# UWB_Control.net
KiCad netlist of a schematic drawn in Altium Designer
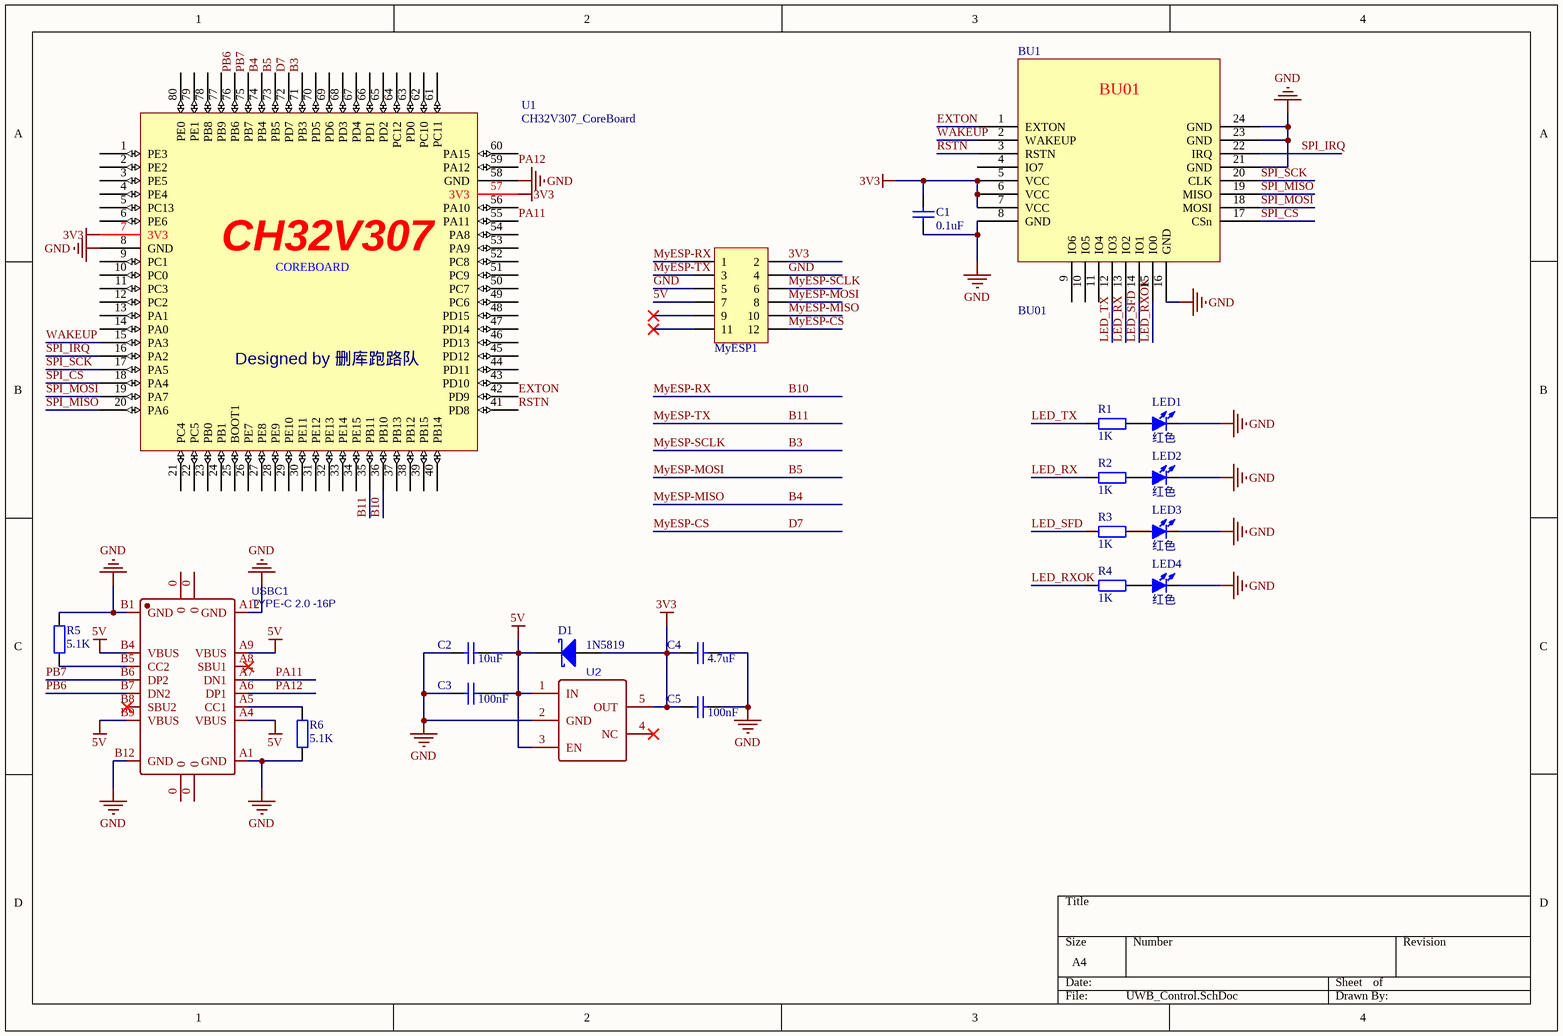
[diagram p0: UWB_Control.SchDoc]

(export (version "E")
  (design (tool "Eeschema 10.0.6"))
  (components
    (comp (ref "BU1") (value "BU01") (footprint "BU01 - duplicate") (libsource (lib "MySch") (part "BU01")))
    (comp (ref "C1")
      (value "0.1uF")
      (footprint "C0805_L")
      (description "贴片电容/MLCC电容")
      (libsource (lib "0.1 - 电阻-电容-电感-晶振-晶体-磁珠-电位器-法拉电容-馈通电容") (part "C"))
    )
    (comp (ref "C2")
      (value "10uF")
      (footprint "C0805_L")
      (description "贴片电容/MLCC电容")
      (libsource (lib "0.1 - 电阻-电容-电感-晶振-晶体-磁珠-电位器-法拉电容-馈通电容") (part "C"))
    )
    (comp (ref "C3")
      (value "100nF")
      (footprint "C0805_L")
      (description "贴片电容/MLCC电容")
      (libsource (lib "0.1 - 电阻-电容-电感-晶振-晶体-磁珠-电位器-法拉电容-馈通电容") (part "C"))
    )
    (comp (ref "C4")
      (value "4.7uF")
      (footprint "C0805_L")
      (description "贴片电容/MLCC电容")
      (libsource (lib "0.1 - 电阻-电容-电感-晶振-晶体-磁珠-电位器-法拉电容-馈通电容") (part "C"))
    )
    (comp (ref "C5")
      (value "100nF")
      (footprint "C0805_L")
      (description "贴片电容/MLCC电容")
      (libsource (lib "0.1 - 电阻-电容-电感-晶振-晶体-磁珠-电位器-法拉电容-馈通电容") (part "C"))
    )
    (comp (ref "D1")
      (value "1N5819")
      (footprint "SOD-323")
      (description "肖特基二极管")
      (libsource (lib "0.2 - 二极管-TVS-ESD-整流桥-放电管") (part "SS14"))
    )
    (comp (ref "LED1")
      (value "红色")
      (footprint "LED0805_G")
      (description "贴片LED")
      (libsource (lib "0.3 - LED发光二极管-IR二极管_接收管-光耦") (part "LED-SMD"))
    )
    (comp (ref "LED2")
      (value "红色")
      (footprint "LED0805_G")
      (description "贴片LED")
      (libsource (lib "0.3 - LED发光二极管-IR二极管_接收管-光耦") (part "LED-SMD"))
    )
    (comp (ref "LED3")
      (value "红色")
      (footprint "LED0805_G")
      (description "贴片LED")
      (libsource (lib "0.3 - LED发光二极管-IR二极管_接收管-光耦") (part "LED-SMD"))
    )
    (comp (ref "LED4")
      (value "红色")
      (footprint "LED0805_G")
      (description "贴片LED")
      (libsource (lib "0.3 - LED发光二极管-IR二极管_接收管-光耦") (part "LED-SMD"))
    )
    (comp (ref "MyESP1")
      (value "Header 6X2")
      (footprint "HDR2.54-M-LS-2x6P")
      (description "6*2P接插件")
      (fields (field (name "版权归属") "封装库来自淘宝 ID：黄晶宝石"))
      (libsource (lib "5.4 - 接插件-脚距2.54 (100mil) ") (part "Header  6X2"))
    )
    (comp (ref "R1")
      (value "1K")
      (footprint "R0805_L")
      (description "贴片电阻")
      (libsource (lib "0.1 - 电阻-电容-电感-晶振-晶体-磁珠-电位器-法拉电容-馈通电容") (part "R"))
    )
    (comp (ref "R2")
      (value "1K")
      (footprint "R0805_L")
      (description "贴片电阻")
      (libsource (lib "0.1 - 电阻-电容-电感-晶振-晶体-磁珠-电位器-法拉电容-馈通电容") (part "R"))
    )
    (comp (ref "R3")
      (value "1K")
      (footprint "R0805_L")
      (description "贴片电阻")
      (libsource (lib "0.1 - 电阻-电容-电感-晶振-晶体-磁珠-电位器-法拉电容-馈通电容") (part "R"))
    )
    (comp (ref "R4")
      (value "1K")
      (footprint "R0805_L")
      (description "贴片电阻")
      (libsource (lib "0.1 - 电阻-电容-电感-晶振-晶体-磁珠-电位器-法拉电容-馈通电容") (part "R"))
    )
    (comp (ref "R5")
      (value "5.1K")
      (footprint "R0402_L")
      (description "贴片电阻")
      (libsource (lib "0.1 - 电阻-电容-电感-晶振-晶体-磁珠-电位器-法拉电容-馈通电容") (part "R"))
    )
    (comp (ref "R6")
      (value "5.1K")
      (footprint "R0402_L")
      (description "贴片电阻")
      (libsource (lib "0.1 - 电阻-电容-电感-晶振-晶体-磁珠-电位器-法拉电容-馈通电容") (part "R"))
    )
    (comp (ref "U1")
      (value "CH32V307_CoreBoard")
      (footprint "CH32V307_PCB")
      (libsource (lib "CH32V307_SCH") (part "CH32V307_CoreBoard"))
    )
    (comp (ref "U2")
      (value "~")
      (footprint "SOT23-5")
      (libsource (lib "altium-import") (part "root_0_RT9013-33_"))
    )
    (comp (ref "USBC1")
      (value "TYPE-C 2.0 -16P")
      (footprint "USB-C-SMD_TYPE-C-USB-5")
      (description "USB2.0 Type-C 母座 16Pin")
      (libsource (lib "0.8 - 以太网-音频-USB插座") (part "USB2.0 Type-C 16Pin母座"))
    )
  )
  (nets
    (net (code "1") (name "/B3") (class "Default")
      (node (ref "MyESP1") (pin "6") (pinfunction "6_6") (pintype "passive"))
      (node (ref "U1") (pin "71") (pinfunction "PB3_71") (pintype "bidirectional"))
    )
    (net (code "2") (name "/B4") (class "Default")
      (node (ref "MyESP1") (pin "10") (pinfunction "10_10") (pintype "passive"))
      (node (ref "U1") (pin "74") (pinfunction "PB4_74") (pintype "bidirectional"))
    )
    (net (code "3") (name "/B5") (class "Default")
      (node (ref "MyESP1") (pin "8") (pinfunction "8_8") (pintype "passive"))
      (node (ref "U1") (pin "73") (pinfunction "PB5_73") (pintype "bidirectional"))
    )
    (net (code "4") (name "/B10") (class "Default")
      (node (ref "MyESP1") (pin "1") (pinfunction "1_1") (pintype "passive"))
      (node (ref "U1") (pin "36") (pinfunction "PB10_36") (pintype "bidirectional"))
    )
    (net (code "5") (name "/B11") (class "Default")
      (node (ref "MyESP1") (pin "3") (pinfunction "3_3") (pintype "passive"))
      (node (ref "U1") (pin "35") (pinfunction "PB11_35") (pintype "bidirectional"))
    )
    (net (code "6") (name "/D7") (class "Default")
      (node (ref "MyESP1") (pin "12") (pinfunction "12_12") (pintype "passive"))
      (node (ref "U1") (pin "72") (pinfunction "PD7_72") (pintype "bidirectional"))
    )
    (net (code "7") (name "/EXTON") (class "Default")
      (node (ref "BU1") (pin "1") (pinfunction "EXTON_1") (pintype "passive"))
      (node (ref "U1") (pin "42") (pinfunction "PD9_42") (pintype "bidirectional"))
    )
    (net (code "8") (name "/LED_RX") (class "Default")
      (node (ref "BU1") (pin "13") (pinfunction "IO2_13") (pintype "passive"))
      (node (ref "R2") (pin "1") (pinfunction "1_1") (pintype "passive"))
    )
    (net (code "9") (name "/LED_RXOK") (class "Default")
      (node (ref "BU1") (pin "15") (pinfunction "IO0_15") (pintype "passive"))
      (node (ref "R4") (pin "1") (pinfunction "1_1") (pintype "passive"))
    )
    (net (code "10") (name "/LED_SFD") (class "Default")
      (node (ref "BU1") (pin "14") (pinfunction "IO1_14") (pintype "passive"))
      (node (ref "R3") (pin "1") (pinfunction "1_1") (pintype "passive"))
    )
    (net (code "11") (name "/LED_TX") (class "Default")
      (node (ref "BU1") (pin "12") (pinfunction "IO3_12") (pintype "passive"))
      (node (ref "R1") (pin "1") (pinfunction "1_1") (pintype "passive"))
    )
    (net (code "12") (name "/PA11") (class "Default")
      (node (ref "U1") (pin "55") (pinfunction "PA11_55") (pintype "bidirectional"))
      (node (ref "USBC1") (pin "A7") (pinfunction "DN1_A7") (pintype "passive"))
    )
    (net (code "13") (name "/PA12") (class "Default")
      (node (ref "U1") (pin "59") (pinfunction "PA12_59") (pintype "bidirectional"))
      (node (ref "USBC1") (pin "A6") (pinfunction "DP1_A6") (pintype "passive"))
    )
    (net (code "14") (name "/PB6") (class "Default")
      (node (ref "U1") (pin "76") (pinfunction "PB6_76") (pintype "bidirectional"))
      (node (ref "USBC1") (pin "B7") (pinfunction "DN2_B7") (pintype "passive"))
    )
    (net (code "15") (name "/PB7") (class "Default")
      (node (ref "U1") (pin "75") (pinfunction "PB7_75") (pintype "bidirectional"))
      (node (ref "USBC1") (pin "B6") (pinfunction "DP2_B6") (pintype "passive"))
    )
    (net (code "16") (name "/RSTN") (class "Default")
      (node (ref "BU1") (pin "3") (pinfunction "RSTN_3") (pintype "passive"))
      (node (ref "U1") (pin "41") (pinfunction "PD8_41") (pintype "bidirectional"))
    )
    (net (code "17") (name "/SPI_CS") (class "Default")
      (node (ref "BU1") (pin "17") (pinfunction "CSn_17") (pintype "passive"))
      (node (ref "U1") (pin "18") (pinfunction "PA4_18") (pintype "bidirectional"))
    )
    (net (code "18") (name "/SPI_IRQ") (class "Default")
      (node (ref "BU1") (pin "22") (pinfunction "IRQ_22") (pintype "passive"))
      (node (ref "U1") (pin "16") (pinfunction "PA2_16") (pintype "bidirectional"))
    )
    (net (code "19") (name "/SPI_MISO") (class "Default")
      (node (ref "BU1") (pin "19") (pinfunction "MISO_19") (pintype "passive"))
      (node (ref "U1") (pin "20") (pinfunction "PA6_20") (pintype "bidirectional"))
    )
    (net (code "20") (name "/SPI_MOSI") (class "Default")
      (node (ref "BU1") (pin "18") (pinfunction "MOSI_18") (pintype "passive"))
      (node (ref "U1") (pin "19") (pinfunction "PA7_19") (pintype "bidirectional"))
    )
    (net (code "21") (name "/SPI_SCK") (class "Default")
      (node (ref "BU1") (pin "20") (pinfunction "CLK_20") (pintype "passive"))
      (node (ref "U1") (pin "17") (pinfunction "PA5_17") (pintype "bidirectional"))
    )
    (net (code "22") (name "/WAKEUP") (class "Default")
      (node (ref "BU1") (pin "2") (pinfunction "WAKEUP_2") (pintype "passive"))
      (node (ref "U1") (pin "15") (pinfunction "PA3_15") (pintype "bidirectional"))
    )
    (net (code "23") (name "3V3") (class "Default")
      (node (ref "BU1") (pin "5") (pinfunction "VCC_5") (pintype "passive"))
      (node (ref "BU1") (pin "6") (pinfunction "VCC_6") (pintype "passive"))
      (node (ref "BU1") (pin "7") (pinfunction "VCC_7") (pintype "passive"))
      (node (ref "C1") (pin "2") (pinfunction "2_2") (pintype "passive"))
      (node (ref "C4") (pin "2") (pinfunction "2_2") (pintype "passive"))
      (node (ref "C5") (pin "2") (pinfunction "2_2") (pintype "passive"))
      (node (ref "D1") (pin "1") (pinfunction "A_1") (pintype "passive"))
      (node (ref "MyESP1") (pin "2") (pinfunction "2_2") (pintype "passive"))
      (node (ref "U1") (pin "57") (pinfunction "3V3_57") (pintype "passive"))
      (node (ref "U1") (pin "7") (pinfunction "3V3_7") (pintype "passive"))
      (node (ref "U2") (pin "5") (pinfunction "OUT_5") (pintype "passive"))
    )
    (net (code "24") (name "5V") (class "Default")
      (node (ref "C2") (pin "1") (pinfunction "1_1") (pintype "passive"))
      (node (ref "C3") (pin "1") (pinfunction "1_1") (pintype "passive"))
      (node (ref "D1") (pin "2") (pinfunction "K_2") (pintype "passive"))
      (node (ref "MyESP1") (pin "7") (pinfunction "7_7") (pintype "passive"))
      (node (ref "U2") (pin "1") (pinfunction "IN_1") (pintype "passive"))
      (node (ref "U2") (pin "3") (pinfunction "EN_3") (pintype "passive"))
      (node (ref "USBC1") (pin "A4") (pinfunction "VBUS_A4") (pintype "passive"))
      (node (ref "USBC1") (pin "A9") (pinfunction "VBUS_A9") (pintype "passive"))
      (node (ref "USBC1") (pin "B4") (pinfunction "VBUS_B4") (pintype "passive"))
      (node (ref "USBC1") (pin "B9") (pinfunction "VBUS_B9") (pintype "passive"))
    )
    (net (code "25") (name "GND") (class "Default")
      (node (ref "BU1") (pin "16") (pinfunction "GND_16") (pintype "passive"))
      (node (ref "BU1") (pin "21") (pinfunction "GND_21") (pintype "passive"))
      (node (ref "BU1") (pin "23") (pinfunction "GND_23") (pintype "passive"))
      (node (ref "BU1") (pin "24") (pinfunction "GND_24") (pintype "passive"))
      (node (ref "BU1") (pin "8") (pinfunction "GND_8") (pintype "passive"))
      (node (ref "C1") (pin "1") (pinfunction "1_1") (pintype "passive"))
      (node (ref "C2") (pin "2") (pinfunction "2_2") (pintype "passive"))
      (node (ref "C3") (pin "2") (pinfunction "2_2") (pintype "passive"))
      (node (ref "C4") (pin "1") (pinfunction "1_1") (pintype "passive"))
      (node (ref "C5") (pin "1") (pinfunction "1_1") (pintype "passive"))
      (node (ref "LED1") (pin "2") (pinfunction "K_2") (pintype "passive"))
      (node (ref "LED2") (pin "2") (pinfunction "K_2") (pintype "passive"))
      (node (ref "LED3") (pin "2") (pinfunction "K_2") (pintype "passive"))
      (node (ref "LED4") (pin "2") (pinfunction "K_2") (pintype "passive"))
      (node (ref "MyESP1") (pin "4") (pinfunction "4_4") (pintype "passive"))
      (node (ref "MyESP1") (pin "5") (pinfunction "5_5") (pintype "passive"))
      (node (ref "R5") (pin "2") (pinfunction "2_2") (pintype "passive"))
      (node (ref "R6") (pin "1") (pinfunction "1_1") (pintype "passive"))
      (node (ref "U1") (pin "58") (pinfunction "GND_58") (pintype "passive"))
      (node (ref "U1") (pin "8") (pinfunction "GND_8") (pintype "passive"))
      (node (ref "U2") (pin "2") (pinfunction "GND_2") (pintype "passive"))
      (node (ref "USBC1") (pin "A1") (pinfunction "GND_A1") (pintype "passive"))
      (node (ref "USBC1") (pin "A12") (pinfunction "GND_A12") (pintype "passive"))
      (node (ref "USBC1") (pin "B1") (pinfunction "GND_B1") (pintype "passive"))
      (node (ref "USBC1") (pin "B12") (pinfunction "GND_B12") (pintype "passive"))
    )
    (net (code "26") (name "Net-(LED1-A)") (class "Default")
      (node (ref "LED1") (pin "1") (pinfunction "A_1") (pintype "passive"))
      (node (ref "R1") (pin "2") (pinfunction "2_2") (pintype "passive"))
    )
    (net (code "27") (name "Net-(LED2-A)") (class "Default")
      (node (ref "LED2") (pin "1") (pinfunction "A_1") (pintype "passive"))
      (node (ref "R2") (pin "2") (pinfunction "2_2") (pintype "passive"))
    )
    (net (code "28") (name "Net-(LED3-A)") (class "Default")
      (node (ref "LED3") (pin "1") (pinfunction "A_1") (pintype "passive"))
      (node (ref "R3") (pin "2") (pinfunction "2_2") (pintype "passive"))
    )
    (net (code "29") (name "Net-(LED4-A)") (class "Default")
      (node (ref "LED4") (pin "1") (pinfunction "A_1") (pintype "passive"))
      (node (ref "R4") (pin "2") (pinfunction "2_2") (pintype "passive"))
    )
    (net (code "30") (name "Net-(USBC1-CC1)") (class "Default")
      (node (ref "R6") (pin "2") (pinfunction "2_2") (pintype "passive"))
      (node (ref "USBC1") (pin "A5") (pinfunction "CC1_A5") (pintype "passive"))
    )
    (net (code "31") (name "Net-(USBC1-CC2)") (class "Default")
      (node (ref "R5") (pin "1") (pinfunction "1_1") (pintype "passive"))
      (node (ref "USBC1") (pin "B5") (pinfunction "CC2_B5") (pintype "passive"))
    )
    (net (code "32") (name "unconnected-(BU1-IO4-Pad11)") (class "Default")
      (node (ref "BU1") (pin "11") (pinfunction "IO4_11") (pintype "passive"))
    )
    (net (code "33") (name "unconnected-(BU1-IO5-Pad10)") (class "Default")
      (node (ref "BU1") (pin "10") (pinfunction "IO5_10") (pintype "passive"))
    )
    (net (code "34") (name "unconnected-(BU1-IO6-Pad9)") (class "Default")
      (node (ref "BU1") (pin "9") (pinfunction "IO6_9") (pintype "passive"))
    )
    (net (code "35") (name "unconnected-(BU1-IO7-Pad4)") (class "Default")
      (node (ref "BU1") (pin "4") (pinfunction "IO7_4") (pintype "passive"))
    )
    (net (code "36") (name "unconnected-(MyESP1-Pad9)") (class "Default")
      (node (ref "MyESP1") (pin "9") (pinfunction "9_9") (pintype "passive+no_connect"))
    )
    (net (code "37") (name "unconnected-(MyESP1-Pad11)") (class "Default")
      (node (ref "MyESP1") (pin "11") (pinfunction "11_11") (pintype "passive+no_connect"))
    )
    (net (code "38") (name "unconnected-(U1-BOOT1-Pad25)") (class "Default")
      (node (ref "U1") (pin "25") (pinfunction "BOOT1_25") (pintype "bidirectional"))
    )
    (net (code "39") (name "unconnected-(U1-PA0-Pad14)") (class "Default")
      (node (ref "U1") (pin "14") (pinfunction "PA0_14") (pintype "bidirectional"))
    )
    (net (code "40") (name "unconnected-(U1-PA1-Pad13)") (class "Default")
      (node (ref "U1") (pin "13") (pinfunction "PA1_13") (pintype "bidirectional"))
    )
    (net (code "41") (name "unconnected-(U1-PA8-Pad54)") (class "Default")
      (node (ref "U1") (pin "54") (pinfunction "PA8_54") (pintype "bidirectional"))
    )
    (net (code "42") (name "unconnected-(U1-PA9-Pad53)") (class "Default")
      (node (ref "U1") (pin "53") (pinfunction "PA9_53") (pintype "bidirectional"))
    )
    (net (code "43") (name "unconnected-(U1-PA10-Pad56)") (class "Default")
      (node (ref "U1") (pin "56") (pinfunction "PA10_56") (pintype "bidirectional"))
    )
    (net (code "44") (name "unconnected-(U1-PA15-Pad60)") (class "Default")
      (node (ref "U1") (pin "60") (pinfunction "PA15_60") (pintype "bidirectional"))
    )
    (net (code "45") (name "unconnected-(U1-PB0-Pad23)") (class "Default")
      (node (ref "U1") (pin "23") (pinfunction "PB0_23") (pintype "bidirectional"))
    )
    (net (code "46") (name "unconnected-(U1-PB1-Pad24)") (class "Default")
      (node (ref "U1") (pin "24") (pinfunction "PB1_24") (pintype "bidirectional"))
    )
    (net (code "47") (name "unconnected-(U1-PB8-Pad78)") (class "Default")
      (node (ref "U1") (pin "78") (pinfunction "PB8_78") (pintype "bidirectional"))
    )
    (net (code "48") (name "unconnected-(U1-PB9-Pad77)") (class "Default")
      (node (ref "U1") (pin "77") (pinfunction "PB9_77") (pintype "bidirectional"))
    )
    (net (code "49") (name "unconnected-(U1-PB12-Pad38)") (class "Default")
      (node (ref "U1") (pin "38") (pinfunction "PB12_38") (pintype "bidirectional"))
    )
    (net (code "50") (name "unconnected-(U1-PB13-Pad37)") (class "Default")
      (node (ref "U1") (pin "37") (pinfunction "PB13_37") (pintype "bidirectional"))
    )
    (net (code "51") (name "unconnected-(U1-PB14-Pad40)") (class "Default")
      (node (ref "U1") (pin "40") (pinfunction "PB14_40") (pintype "bidirectional"))
    )
    (net (code "52") (name "unconnected-(U1-PB15-Pad39)") (class "Default")
      (node (ref "U1") (pin "39") (pinfunction "PB15_39") (pintype "bidirectional"))
    )
    (net (code "53") (name "unconnected-(U1-PC0-Pad10)") (class "Default")
      (node (ref "U1") (pin "10") (pinfunction "PC0_10") (pintype "bidirectional"))
    )
    (net (code "54") (name "unconnected-(U1-PC1-Pad9)") (class "Default")
      (node (ref "U1") (pin "9") (pinfunction "PC1_9") (pintype "bidirectional"))
    )
    (net (code "55") (name "unconnected-(U1-PC2-Pad12)") (class "Default")
      (node (ref "U1") (pin "12") (pinfunction "PC2_12") (pintype "bidirectional"))
    )
    (net (code "56") (name "unconnected-(U1-PC3-Pad11)") (class "Default")
      (node (ref "U1") (pin "11") (pinfunction "PC3_11") (pintype "bidirectional"))
    )
    (net (code "57") (name "unconnected-(U1-PC4-Pad21)") (class "Default")
      (node (ref "U1") (pin "21") (pinfunction "PC4_21") (pintype "bidirectional"))
    )
    (net (code "58") (name "unconnected-(U1-PC5-Pad22)") (class "Default")
      (node (ref "U1") (pin "22") (pinfunction "PC5_22") (pintype "bidirectional"))
    )
    (net (code "59") (name "unconnected-(U1-PC6-Pad49)") (class "Default")
      (node (ref "U1") (pin "49") (pinfunction "PC6_49") (pintype "bidirectional"))
    )
    (net (code "60") (name "unconnected-(U1-PC7-Pad50)") (class "Default")
      (node (ref "U1") (pin "50") (pinfunction "PC7_50") (pintype "bidirectional"))
    )
    (net (code "61") (name "unconnected-(U1-PC8-Pad52)") (class "Default")
      (node (ref "U1") (pin "52") (pinfunction "PC8_52") (pintype "bidirectional"))
    )
    (net (code "62") (name "unconnected-(U1-PC9-Pad51)") (class "Default")
      (node (ref "U1") (pin "51") (pinfunction "PC9_51") (pintype "bidirectional"))
    )
    (net (code "63") (name "unconnected-(U1-PC10-Pad62)") (class "Default")
      (node (ref "U1") (pin "62") (pinfunction "PC10_62") (pintype "bidirectional"))
    )
    (net (code "64") (name "unconnected-(U1-PC11-Pad61)") (class "Default")
      (node (ref "U1") (pin "61") (pinfunction "PC11_61") (pintype "bidirectional"))
    )
    (net (code "65") (name "unconnected-(U1-PC12-Pad64)") (class "Default")
      (node (ref "U1") (pin "64") (pinfunction "PC12_64") (pintype "bidirectional"))
    )
    (net (code "66") (name "unconnected-(U1-PC13-Pad5)") (class "Default")
      (node (ref "U1") (pin "5") (pinfunction "PC13_5") (pintype "bidirectional"))
    )
    (net (code "67") (name "unconnected-(U1-PD0-Pad63)") (class "Default")
      (node (ref "U1") (pin "63") (pinfunction "PD0_63") (pintype "bidirectional"))
    )
    (net (code "68") (name "unconnected-(U1-PD1-Pad66)") (class "Default")
      (node (ref "U1") (pin "66") (pinfunction "PD1_66") (pintype "bidirectional"))
    )
    (net (code "69") (name "unconnected-(U1-PD2-Pad65)") (class "Default")
      (node (ref "U1") (pin "65") (pinfunction "PD2_65") (pintype "bidirectional"))
    )
    (net (code "70") (name "unconnected-(U1-PD3-Pad68)") (class "Default")
      (node (ref "U1") (pin "68") (pinfunction "PD3_68") (pintype "bidirectional"))
    )
    (net (code "71") (name "unconnected-(U1-PD4-Pad67)") (class "Default")
      (node (ref "U1") (pin "67") (pinfunction "PD4_67") (pintype "bidirectional"))
    )
    (net (code "72") (name "unconnected-(U1-PD5-Pad70)") (class "Default")
      (node (ref "U1") (pin "70") (pinfunction "PD5_70") (pintype "bidirectional"))
    )
    (net (code "73") (name "unconnected-(U1-PD6-Pad69)") (class "Default")
      (node (ref "U1") (pin "69") (pinfunction "PD6_69") (pintype "bidirectional"))
    )
    (net (code "74") (name "unconnected-(U1-PD10-Pad43)") (class "Default")
      (node (ref "U1") (pin "43") (pinfunction "PD10_43") (pintype "bidirectional"))
    )
    (net (code "75") (name "unconnected-(U1-PD11-Pad44)") (class "Default")
      (node (ref "U1") (pin "44") (pinfunction "PD11_44") (pintype "bidirectional"))
    )
    (net (code "76") (name "unconnected-(U1-PD12-Pad45)") (class "Default")
      (node (ref "U1") (pin "45") (pinfunction "PD12_45") (pintype "bidirectional"))
    )
    (net (code "77") (name "unconnected-(U1-PD13-Pad46)") (class "Default")
      (node (ref "U1") (pin "46") (pinfunction "PD13_46") (pintype "bidirectional"))
    )
    (net (code "78") (name "unconnected-(U1-PD14-Pad47)") (class "Default")
      (node (ref "U1") (pin "47") (pinfunction "PD14_47") (pintype "bidirectional"))
    )
    (net (code "79") (name "unconnected-(U1-PD15-Pad48)") (class "Default")
      (node (ref "U1") (pin "48") (pinfunction "PD15_48") (pintype "bidirectional"))
    )
    (net (code "80") (name "unconnected-(U1-PE0-Pad80)") (class "Default")
      (node (ref "U1") (pin "80") (pinfunction "PE0_80") (pintype "bidirectional"))
    )
    (net (code "81") (name "unconnected-(U1-PE1-Pad79)") (class "Default")
      (node (ref "U1") (pin "79") (pinfunction "PE1_79") (pintype "bidirectional"))
    )
    (net (code "82") (name "unconnected-(U1-PE2-Pad2)") (class "Default")
      (node (ref "U1") (pin "2") (pinfunction "PE2_2") (pintype "bidirectional"))
    )
    (net (code "83") (name "unconnected-(U1-PE3-Pad1)") (class "Default")
      (node (ref "U1") (pin "1") (pinfunction "PE3_1") (pintype "bidirectional"))
    )
    (net (code "84") (name "unconnected-(U1-PE4-Pad4)") (class "Default")
      (node (ref "U1") (pin "4") (pinfunction "PE4_4") (pintype "bidirectional"))
    )
    (net (code "85") (name "unconnected-(U1-PE5-Pad3)") (class "Default")
      (node (ref "U1") (pin "3") (pinfunction "PE5_3") (pintype "bidirectional"))
    )
    (net (code "86") (name "unconnected-(U1-PE6-Pad6)") (class "Default")
      (node (ref "U1") (pin "6") (pinfunction "PE6_6") (pintype "bidirectional"))
    )
    (net (code "87") (name "unconnected-(U1-PE7-Pad26)") (class "Default")
      (node (ref "U1") (pin "26") (pinfunction "PE7_26") (pintype "bidirectional"))
    )
    (net (code "88") (name "unconnected-(U1-PE8-Pad27)") (class "Default")
      (node (ref "U1") (pin "27") (pinfunction "PE8_27") (pintype "bidirectional"))
    )
    (net (code "89") (name "unconnected-(U1-PE9-Pad28)") (class "Default")
      (node (ref "U1") (pin "28") (pinfunction "PE9_28") (pintype "bidirectional"))
    )
    (net (code "90") (name "unconnected-(U1-PE10-Pad29)") (class "Default")
      (node (ref "U1") (pin "29") (pinfunction "PE10_29") (pintype "bidirectional"))
    )
    (net (code "91") (name "unconnected-(U1-PE11-Pad30)") (class "Default")
      (node (ref "U1") (pin "30") (pinfunction "PE11_30") (pintype "bidirectional"))
    )
    (net (code "92") (name "unconnected-(U1-PE12-Pad31)") (class "Default")
      (node (ref "U1") (pin "31") (pinfunction "PE12_31") (pintype "bidirectional"))
    )
    (net (code "93") (name "unconnected-(U1-PE13-Pad32)") (class "Default")
      (node (ref "U1") (pin "32") (pinfunction "PE13_32") (pintype "bidirectional"))
    )
    (net (code "94") (name "unconnected-(U1-PE14-Pad33)") (class "Default")
      (node (ref "U1") (pin "33") (pinfunction "PE14_33") (pintype "bidirectional"))
    )
    (net (code "95") (name "unconnected-(U1-PE15-Pad34)") (class "Default")
      (node (ref "U1") (pin "34") (pinfunction "PE15_34") (pintype "bidirectional"))
    )
    (net (code "96") (name "unconnected-(U2-NC-Pad4)") (class "Default")
      (node (ref "U2") (pin "4") (pinfunction "NC_4") (pintype "passive+no_connect"))
    )
    (net (code "97") (name "unconnected-(USBC1-Pad0)") (class "Default")
      (node (ref "USBC1") (pin "0") (pinfunction "0_0") (pintype "passive"))
    )
    (net (code "98") (name "unconnected-(USBC1-Pad0)_1") (class "Default")
      (node (ref "USBC1") (pin "0") (pinfunction "0_0") (pintype "passive"))
    )
    (net (code "99") (name "unconnected-(USBC1-Pad0)_2") (class "Default")
      (node (ref "USBC1") (pin "0") (pinfunction "0_0") (pintype "passive"))
    )
    (net (code "100") (name "unconnected-(USBC1-Pad0)_3") (class "Default")
      (node (ref "USBC1") (pin "0") (pinfunction "0_0") (pintype "passive"))
    )
    (net (code "101") (name "unconnected-(USBC1-SBU1-PadA8)") (class "Default")
      (node (ref "USBC1") (pin "A8") (pinfunction "SBU1_A8") (pintype "passive+no_connect"))
    )
    (net (code "102") (name "unconnected-(USBC1-SBU2-PadB8)") (class "Default")
      (node (ref "USBC1") (pin "B8") (pinfunction "SBU2_B8") (pintype "passive+no_connect"))
    )
  )
)
